# IORELAY8.net
KiCad netlist of a schematic drawn in EAGLE
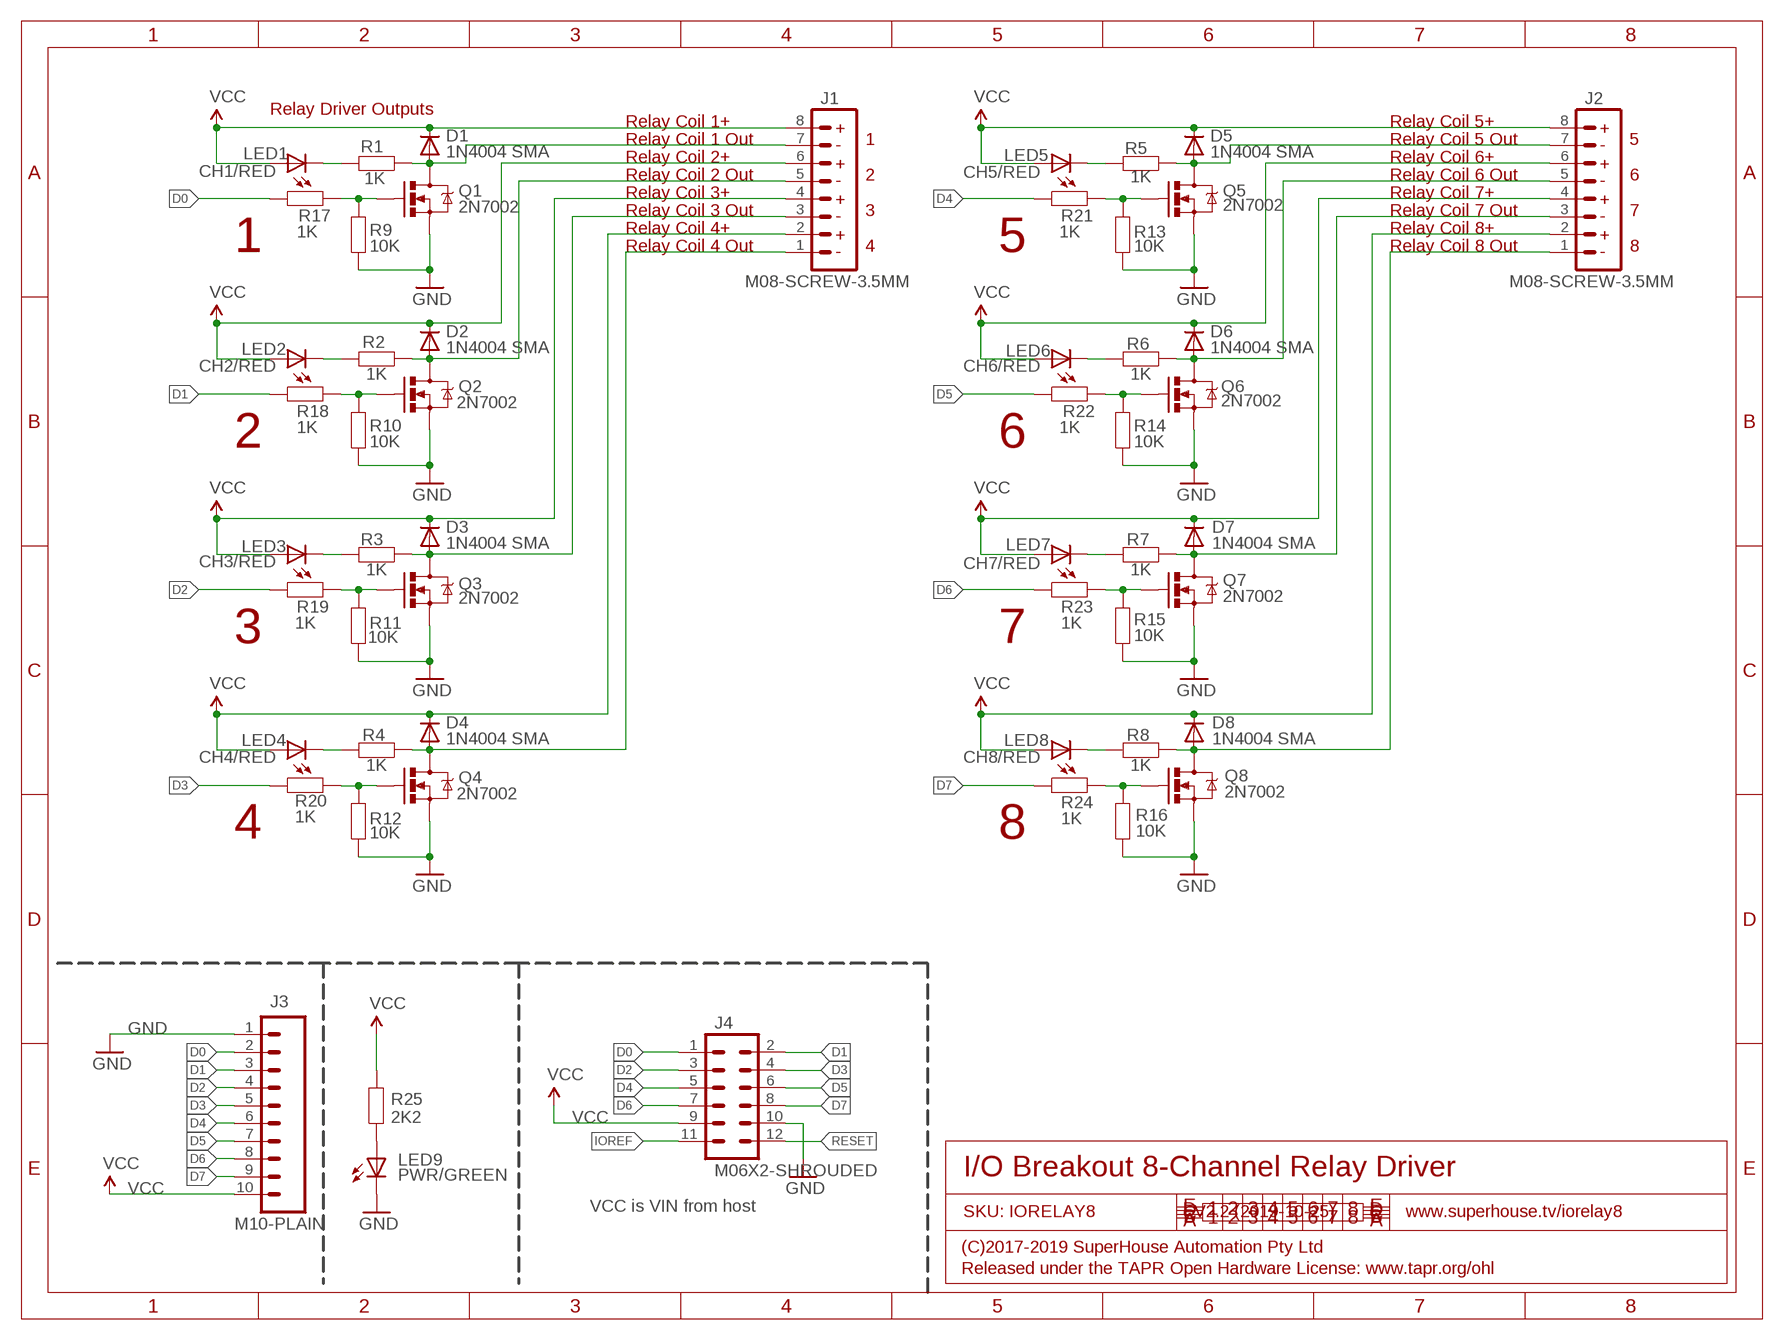
[diagram p0: schematic, sheet 1]

(export (version "E")
  (design (tool "Eeschema 10.0.6"))
  (components
    (comp (ref "D1")
      (value "1N4004 SMA")
      (footprint "eagle-import:SMA-DIODE")
      (libsource (lib "eagle-import") (part "DIODESMA"))
    )
    (comp (ref "D2")
      (value "1N4004 SMA")
      (footprint "eagle-import:SMA-DIODE")
      (libsource (lib "eagle-import") (part "DIODESMA"))
    )
    (comp (ref "D3")
      (value "1N4004 SMA")
      (footprint "eagle-import:SMA-DIODE")
      (libsource (lib "eagle-import") (part "DIODESMA"))
    )
    (comp (ref "D4")
      (value "1N4004 SMA")
      (footprint "eagle-import:SMA-DIODE")
      (libsource (lib "eagle-import") (part "DIODESMA"))
    )
    (comp (ref "D5")
      (value "1N4004 SMA")
      (footprint "eagle-import:SMA-DIODE")
      (libsource (lib "eagle-import") (part "DIODESMA"))
    )
    (comp (ref "D6")
      (value "1N4004 SMA")
      (footprint "eagle-import:SMA-DIODE")
      (libsource (lib "eagle-import") (part "DIODESMA"))
    )
    (comp (ref "D7")
      (value "1N4004 SMA")
      (footprint "eagle-import:SMA-DIODE")
      (libsource (lib "eagle-import") (part "DIODESMA"))
    )
    (comp (ref "D8")
      (value "1N4004 SMA")
      (footprint "eagle-import:SMA-DIODE")
      (libsource (lib "eagle-import") (part "DIODESMA"))
    )
    (comp (ref "J1")
      (value "M08-SCREW-3.5MM")
      (footprint "eagle-import:SCREWTERMINAL_3.5MM_8")
      (libsource (lib "eagle-import") (part "M08-SCREW-3.5MM"))
    )
    (comp (ref "J2")
      (value "M08-SCREW-3.5MM")
      (footprint "eagle-import:SCREWTERMINAL_3.5MM_8")
      (libsource (lib "eagle-import") (part "M08-SCREW-3.5MM"))
    )
    (comp (ref "J3")
      (value "M10-PLAIN")
      (footprint "eagle-import:1X10")
      (libsource (lib "eagle-import") (part "M10-PLAIN"))
    )
    (comp (ref "J4")
      (value "M06X2-SHROUDED")
      (footprint "eagle-import:2X6-SHROUDED")
      (libsource (lib "eagle-import") (part "M06X2-SHROUDED"))
    )
    (comp (ref "LED1")
      (value "CH1/RED")
      (footprint "eagle-import:LED-0603")
      (libsource (lib "eagle-import") (part "LED0603"))
    )
    (comp (ref "LED2")
      (value "CH2/RED")
      (footprint "eagle-import:LED-0603")
      (libsource (lib "eagle-import") (part "LED0603"))
    )
    (comp (ref "LED3")
      (value "CH3/RED")
      (footprint "eagle-import:LED-0603")
      (libsource (lib "eagle-import") (part "LED0603"))
    )
    (comp (ref "LED4")
      (value "CH4/RED")
      (footprint "eagle-import:LED-0603")
      (libsource (lib "eagle-import") (part "LED0603"))
    )
    (comp (ref "LED5")
      (value "CH5/RED")
      (footprint "eagle-import:LED-0603")
      (libsource (lib "eagle-import") (part "LED0603"))
    )
    (comp (ref "LED6")
      (value "CH6/RED")
      (footprint "eagle-import:LED-0603")
      (libsource (lib "eagle-import") (part "LED0603"))
    )
    (comp (ref "LED7")
      (value "CH7/RED")
      (footprint "eagle-import:LED-0603")
      (libsource (lib "eagle-import") (part "LED0603"))
    )
    (comp (ref "LED8")
      (value "CH8/RED")
      (footprint "eagle-import:LED-0603")
      (libsource (lib "eagle-import") (part "LED0603"))
    )
    (comp (ref "LED9")
      (value "PWR/GREEN")
      (footprint "eagle-import:LED-0603")
      (libsource (lib "eagle-import") (part "LED0603"))
    )
    (comp (ref "Q1")
      (value "2N7002")
      (footprint "eagle-import:SOT23-3")
      (libsource (lib "eagle-import") (part "MOSFET-NCHANNEL-233"))
    )
    (comp (ref "Q2")
      (value "2N7002")
      (footprint "eagle-import:SOT23-3")
      (libsource (lib "eagle-import") (part "MOSFET-NCHANNEL-233"))
    )
    (comp (ref "Q3")
      (value "2N7002")
      (footprint "eagle-import:SOT23-3")
      (libsource (lib "eagle-import") (part "MOSFET-NCHANNEL-233"))
    )
    (comp (ref "Q4")
      (value "2N7002")
      (footprint "eagle-import:SOT23-3")
      (libsource (lib "eagle-import") (part "MOSFET-NCHANNEL-233"))
    )
    (comp (ref "Q5")
      (value "2N7002")
      (footprint "eagle-import:SOT23-3")
      (libsource (lib "eagle-import") (part "MOSFET-NCHANNEL-233"))
    )
    (comp (ref "Q6")
      (value "2N7002")
      (footprint "eagle-import:SOT23-3")
      (libsource (lib "eagle-import") (part "MOSFET-NCHANNEL-233"))
    )
    (comp (ref "Q7")
      (value "2N7002")
      (footprint "eagle-import:SOT23-3")
      (libsource (lib "eagle-import") (part "MOSFET-NCHANNEL-233"))
    )
    (comp (ref "Q8")
      (value "2N7002")
      (footprint "eagle-import:SOT23-3")
      (libsource (lib "eagle-import") (part "MOSFET-NCHANNEL-233"))
    )
    (comp (ref "R1")
      (value "1K")
      (footprint "eagle-import:R0603")
      (libsource (lib "eagle-import") (part "RESISTOR0603"))
    )
    (comp (ref "R2")
      (value "1K")
      (footprint "eagle-import:R0603")
      (libsource (lib "eagle-import") (part "RESISTOR0603"))
    )
    (comp (ref "R3")
      (value "1K")
      (footprint "eagle-import:R0603")
      (libsource (lib "eagle-import") (part "RESISTOR0603"))
    )
    (comp (ref "R4")
      (value "1K")
      (footprint "eagle-import:R0603")
      (libsource (lib "eagle-import") (part "RESISTOR0603"))
    )
    (comp (ref "R5")
      (value "1K")
      (footprint "eagle-import:R0603")
      (libsource (lib "eagle-import") (part "RESISTOR0603"))
    )
    (comp (ref "R6")
      (value "1K")
      (footprint "eagle-import:R0603")
      (libsource (lib "eagle-import") (part "RESISTOR0603"))
    )
    (comp (ref "R7")
      (value "1K")
      (footprint "eagle-import:R0603")
      (libsource (lib "eagle-import") (part "RESISTOR0603"))
    )
    (comp (ref "R8")
      (value "1K")
      (footprint "eagle-import:R0603")
      (libsource (lib "eagle-import") (part "RESISTOR0603"))
    )
    (comp (ref "R9")
      (value "10K")
      (footprint "eagle-import:R0603")
      (libsource (lib "eagle-import") (part "RESISTOR0603"))
    )
    (comp (ref "R10")
      (value "10K")
      (footprint "eagle-import:R0603")
      (libsource (lib "eagle-import") (part "RESISTOR0603"))
    )
    (comp (ref "R11")
      (value "10K")
      (footprint "eagle-import:R0603")
      (libsource (lib "eagle-import") (part "RESISTOR0603"))
    )
    (comp (ref "R12")
      (value "10K")
      (footprint "eagle-import:R0603")
      (libsource (lib "eagle-import") (part "RESISTOR0603"))
    )
    (comp (ref "R13")
      (value "10K")
      (footprint "eagle-import:R0603")
      (libsource (lib "eagle-import") (part "RESISTOR0603"))
    )
    (comp (ref "R14")
      (value "10K")
      (footprint "eagle-import:R0603")
      (libsource (lib "eagle-import") (part "RESISTOR0603"))
    )
    (comp (ref "R15")
      (value "10K")
      (footprint "eagle-import:R0603")
      (libsource (lib "eagle-import") (part "RESISTOR0603"))
    )
    (comp (ref "R16")
      (value "10K")
      (footprint "eagle-import:R0603")
      (libsource (lib "eagle-import") (part "RESISTOR0603"))
    )
    (comp (ref "R17")
      (value "1K")
      (footprint "eagle-import:R0603")
      (libsource (lib "eagle-import") (part "RESISTOR0603"))
    )
    (comp (ref "R18")
      (value "1K")
      (footprint "eagle-import:R0603")
      (libsource (lib "eagle-import") (part "RESISTOR0603"))
    )
    (comp (ref "R19")
      (value "1K")
      (footprint "eagle-import:R0603")
      (libsource (lib "eagle-import") (part "RESISTOR0603"))
    )
    (comp (ref "R20")
      (value "1K")
      (footprint "eagle-import:R0603")
      (libsource (lib "eagle-import") (part "RESISTOR0603"))
    )
    (comp (ref "R21")
      (value "1K")
      (footprint "eagle-import:R0603")
      (libsource (lib "eagle-import") (part "RESISTOR0603"))
    )
    (comp (ref "R22")
      (value "1K")
      (footprint "eagle-import:R0603")
      (libsource (lib "eagle-import") (part "RESISTOR0603"))
    )
    (comp (ref "R23")
      (value "1K")
      (footprint "eagle-import:R0603")
      (libsource (lib "eagle-import") (part "RESISTOR0603"))
    )
    (comp (ref "R24")
      (value "1K")
      (footprint "eagle-import:R0603")
      (libsource (lib "eagle-import") (part "RESISTOR0603"))
    )
    (comp (ref "R25")
      (value "2K2")
      (footprint "eagle-import:R0603")
      (libsource (lib "eagle-import") (part "RESISTOR0603"))
    )
  )
  (nets
    (net (code "1") (name "D0") (class "Default")
      (node (ref "J3") (pin "2") (pinfunction "2_2") (pintype "passive"))
      (node (ref "J4") (pin "1") (pinfunction "1_1") (pintype "passive"))
      (node (ref "R17") (pin "2") (pinfunction "2_2") (pintype "passive"))
    )
    (net (code "2") (name "D1") (class "Default")
      (node (ref "J3") (pin "3") (pinfunction "3_3") (pintype "passive"))
      (node (ref "J4") (pin "2") (pinfunction "2_2") (pintype "passive"))
      (node (ref "R18") (pin "2") (pinfunction "2_2") (pintype "passive"))
    )
    (net (code "3") (name "D2") (class "Default")
      (node (ref "J3") (pin "4") (pinfunction "4_4") (pintype "passive"))
      (node (ref "J4") (pin "3") (pinfunction "3_3") (pintype "passive"))
      (node (ref "R19") (pin "2") (pinfunction "2_2") (pintype "passive"))
    )
    (net (code "4") (name "D3") (class "Default")
      (node (ref "J3") (pin "5") (pinfunction "5_5") (pintype "passive"))
      (node (ref "J4") (pin "4") (pinfunction "4_4") (pintype "passive"))
      (node (ref "R20") (pin "2") (pinfunction "2_2") (pintype "passive"))
    )
    (net (code "5") (name "D4") (class "Default")
      (node (ref "J3") (pin "6") (pinfunction "6_6") (pintype "passive"))
      (node (ref "J4") (pin "5") (pinfunction "5_5") (pintype "passive"))
      (node (ref "R21") (pin "2") (pinfunction "2_2") (pintype "passive"))
    )
    (net (code "6") (name "D5") (class "Default")
      (node (ref "J3") (pin "7") (pinfunction "7_7") (pintype "passive"))
      (node (ref "J4") (pin "6") (pinfunction "6_6") (pintype "passive"))
      (node (ref "R22") (pin "2") (pinfunction "2_2") (pintype "passive"))
    )
    (net (code "7") (name "D6") (class "Default")
      (node (ref "J3") (pin "8") (pinfunction "8_8") (pintype "passive"))
      (node (ref "J4") (pin "7") (pinfunction "7_7") (pintype "passive"))
      (node (ref "R23") (pin "2") (pinfunction "2_2") (pintype "passive"))
    )
    (net (code "8") (name "D7") (class "Default")
      (node (ref "J3") (pin "9") (pinfunction "9_9") (pintype "passive"))
      (node (ref "J4") (pin "8") (pinfunction "8_8") (pintype "passive"))
      (node (ref "R24") (pin "2") (pinfunction "2_2") (pintype "passive"))
    )
    (net (code "9") (name "GND") (class "Default")
      (node (ref "J3") (pin "1") (pinfunction "1_1") (pintype "passive"))
      (node (ref "J4") (pin "10") (pinfunction "10_10") (pintype "passive"))
      (node (ref "LED9") (pin "C") (pinfunction "C_C") (pintype "passive"))
      (node (ref "Q1") (pin "2") (pinfunction "S_2") (pintype "passive"))
      (node (ref "Q2") (pin "2") (pinfunction "S_2") (pintype "passive"))
      (node (ref "Q3") (pin "2") (pinfunction "S_2") (pintype "passive"))
      (node (ref "Q4") (pin "2") (pinfunction "S_2") (pintype "passive"))
      (node (ref "Q5") (pin "2") (pinfunction "S_2") (pintype "passive"))
      (node (ref "Q6") (pin "2") (pinfunction "S_2") (pintype "passive"))
      (node (ref "Q7") (pin "2") (pinfunction "S_2") (pintype "passive"))
      (node (ref "Q8") (pin "2") (pinfunction "S_2") (pintype "passive"))
      (node (ref "R10") (pin "1") (pinfunction "1_1") (pintype "passive"))
      (node (ref "R11") (pin "1") (pinfunction "1_1") (pintype "passive"))
      (node (ref "R12") (pin "1") (pinfunction "1_1") (pintype "passive"))
      (node (ref "R13") (pin "1") (pinfunction "1_1") (pintype "passive"))
      (node (ref "R14") (pin "1") (pinfunction "1_1") (pintype "passive"))
      (node (ref "R15") (pin "1") (pinfunction "1_1") (pintype "passive"))
      (node (ref "R16") (pin "1") (pinfunction "1_1") (pintype "passive"))
      (node (ref "R9") (pin "1") (pinfunction "1_1") (pintype "passive"))
    )
    (net (code "10") (name "IOREF") (class "Default")
      (node (ref "J4") (pin "11") (pinfunction "11_11") (pintype "passive"))
    )
    (net (code "11") (name "Net-(LED1-PadC)") (class "Default")
      (node (ref "LED1") (pin "C") (pinfunction "C_C") (pintype "passive"))
      (node (ref "R1") (pin "1") (pinfunction "1_1") (pintype "passive"))
    )
    (net (code "12") (name "Net-(LED2-PadC)") (class "Default")
      (node (ref "LED2") (pin "C") (pinfunction "C_C") (pintype "passive"))
      (node (ref "R2") (pin "1") (pinfunction "1_1") (pintype "passive"))
    )
    (net (code "13") (name "Net-(LED3-PadC)") (class "Default")
      (node (ref "LED3") (pin "C") (pinfunction "C_C") (pintype "passive"))
      (node (ref "R3") (pin "1") (pinfunction "1_1") (pintype "passive"))
    )
    (net (code "14") (name "Net-(LED4-PadC)") (class "Default")
      (node (ref "LED4") (pin "C") (pinfunction "C_C") (pintype "passive"))
      (node (ref "R4") (pin "1") (pinfunction "1_1") (pintype "passive"))
    )
    (net (code "15") (name "Net-(LED5-PadC)") (class "Default")
      (node (ref "LED5") (pin "C") (pinfunction "C_C") (pintype "passive"))
      (node (ref "R5") (pin "1") (pinfunction "1_1") (pintype "passive"))
    )
    (net (code "16") (name "Net-(LED6-PadC)") (class "Default")
      (node (ref "LED6") (pin "C") (pinfunction "C_C") (pintype "passive"))
      (node (ref "R6") (pin "1") (pinfunction "1_1") (pintype "passive"))
    )
    (net (code "17") (name "Net-(LED7-PadC)") (class "Default")
      (node (ref "LED7") (pin "C") (pinfunction "C_C") (pintype "passive"))
      (node (ref "R7") (pin "1") (pinfunction "1_1") (pintype "passive"))
    )
    (net (code "18") (name "Net-(LED8-PadC)") (class "Default")
      (node (ref "LED8") (pin "C") (pinfunction "C_C") (pintype "passive"))
      (node (ref "R8") (pin "1") (pinfunction "1_1") (pintype "passive"))
    )
    (net (code "19") (name "Net-(LED9-PadA)") (class "Default")
      (node (ref "LED9") (pin "A") (pinfunction "A_A") (pintype "passive"))
      (node (ref "R25") (pin "1") (pinfunction "1_1") (pintype "passive"))
    )
    (net (code "20") (name "Net-(Q1-D)") (class "Default")
      (node (ref "D1") (pin "A") (pinfunction "A_A") (pintype "passive"))
      (node (ref "J1") (pin "7") (pinfunction "7_7") (pintype "passive"))
      (node (ref "Q1") (pin "3") (pinfunction "D_3") (pintype "passive"))
      (node (ref "R1") (pin "2") (pinfunction "2_2") (pintype "passive"))
    )
    (net (code "21") (name "Net-(Q1-G)") (class "Default")
      (node (ref "Q1") (pin "1") (pinfunction "G_1") (pintype "passive"))
      (node (ref "R17") (pin "1") (pinfunction "1_1") (pintype "passive"))
      (node (ref "R9") (pin "2") (pinfunction "2_2") (pintype "passive"))
    )
    (net (code "22") (name "Net-(Q2-D)") (class "Default")
      (node (ref "D2") (pin "A") (pinfunction "A_A") (pintype "passive"))
      (node (ref "J1") (pin "5") (pinfunction "5_5") (pintype "passive"))
      (node (ref "Q2") (pin "3") (pinfunction "D_3") (pintype "passive"))
      (node (ref "R2") (pin "2") (pinfunction "2_2") (pintype "passive"))
    )
    (net (code "23") (name "Net-(Q2-G)") (class "Default")
      (node (ref "Q2") (pin "1") (pinfunction "G_1") (pintype "passive"))
      (node (ref "R10") (pin "2") (pinfunction "2_2") (pintype "passive"))
      (node (ref "R18") (pin "1") (pinfunction "1_1") (pintype "passive"))
    )
    (net (code "24") (name "Net-(Q3-D)") (class "Default")
      (node (ref "D3") (pin "A") (pinfunction "A_A") (pintype "passive"))
      (node (ref "J1") (pin "3") (pinfunction "3_3") (pintype "passive"))
      (node (ref "Q3") (pin "3") (pinfunction "D_3") (pintype "passive"))
      (node (ref "R3") (pin "2") (pinfunction "2_2") (pintype "passive"))
    )
    (net (code "25") (name "Net-(Q3-G)") (class "Default")
      (node (ref "Q3") (pin "1") (pinfunction "G_1") (pintype "passive"))
      (node (ref "R11") (pin "2") (pinfunction "2_2") (pintype "passive"))
      (node (ref "R19") (pin "1") (pinfunction "1_1") (pintype "passive"))
    )
    (net (code "26") (name "Net-(Q4-D)") (class "Default")
      (node (ref "D4") (pin "A") (pinfunction "A_A") (pintype "passive"))
      (node (ref "J1") (pin "1") (pinfunction "1_1") (pintype "passive"))
      (node (ref "Q4") (pin "3") (pinfunction "D_3") (pintype "passive"))
      (node (ref "R4") (pin "2") (pinfunction "2_2") (pintype "passive"))
    )
    (net (code "27") (name "Net-(Q4-G)") (class "Default")
      (node (ref "Q4") (pin "1") (pinfunction "G_1") (pintype "passive"))
      (node (ref "R12") (pin "2") (pinfunction "2_2") (pintype "passive"))
      (node (ref "R20") (pin "1") (pinfunction "1_1") (pintype "passive"))
    )
    (net (code "28") (name "Net-(Q5-D)") (class "Default")
      (node (ref "D5") (pin "A") (pinfunction "A_A") (pintype "passive"))
      (node (ref "J2") (pin "7") (pinfunction "7_7") (pintype "passive"))
      (node (ref "Q5") (pin "3") (pinfunction "D_3") (pintype "passive"))
      (node (ref "R5") (pin "2") (pinfunction "2_2") (pintype "passive"))
    )
    (net (code "29") (name "Net-(Q5-G)") (class "Default")
      (node (ref "Q5") (pin "1") (pinfunction "G_1") (pintype "passive"))
      (node (ref "R13") (pin "2") (pinfunction "2_2") (pintype "passive"))
      (node (ref "R21") (pin "1") (pinfunction "1_1") (pintype "passive"))
    )
    (net (code "30") (name "Net-(Q6-D)") (class "Default")
      (node (ref "D6") (pin "A") (pinfunction "A_A") (pintype "passive"))
      (node (ref "J2") (pin "5") (pinfunction "5_5") (pintype "passive"))
      (node (ref "Q6") (pin "3") (pinfunction "D_3") (pintype "passive"))
      (node (ref "R6") (pin "2") (pinfunction "2_2") (pintype "passive"))
    )
    (net (code "31") (name "Net-(Q6-G)") (class "Default")
      (node (ref "Q6") (pin "1") (pinfunction "G_1") (pintype "passive"))
      (node (ref "R14") (pin "2") (pinfunction "2_2") (pintype "passive"))
      (node (ref "R22") (pin "1") (pinfunction "1_1") (pintype "passive"))
    )
    (net (code "32") (name "Net-(Q7-D)") (class "Default")
      (node (ref "D7") (pin "A") (pinfunction "A_A") (pintype "passive"))
      (node (ref "J2") (pin "3") (pinfunction "3_3") (pintype "passive"))
      (node (ref "Q7") (pin "3") (pinfunction "D_3") (pintype "passive"))
      (node (ref "R7") (pin "2") (pinfunction "2_2") (pintype "passive"))
    )
    (net (code "33") (name "Net-(Q7-G)") (class "Default")
      (node (ref "Q7") (pin "1") (pinfunction "G_1") (pintype "passive"))
      (node (ref "R15") (pin "2") (pinfunction "2_2") (pintype "passive"))
      (node (ref "R23") (pin "1") (pinfunction "1_1") (pintype "passive"))
    )
    (net (code "34") (name "Net-(Q8-D)") (class "Default")
      (node (ref "D8") (pin "A") (pinfunction "A_A") (pintype "passive"))
      (node (ref "J2") (pin "1") (pinfunction "1_1") (pintype "passive"))
      (node (ref "Q8") (pin "3") (pinfunction "D_3") (pintype "passive"))
      (node (ref "R8") (pin "2") (pinfunction "2_2") (pintype "passive"))
    )
    (net (code "35") (name "Net-(Q8-G)") (class "Default")
      (node (ref "Q8") (pin "1") (pinfunction "G_1") (pintype "passive"))
      (node (ref "R16") (pin "2") (pinfunction "2_2") (pintype "passive"))
      (node (ref "R24") (pin "1") (pinfunction "1_1") (pintype "passive"))
    )
    (net (code "36") (name "RESET") (class "Default")
      (node (ref "J4") (pin "12") (pinfunction "12_12") (pintype "passive"))
    )
    (net (code "37") (name "VCC") (class "Default")
      (node (ref "D1") (pin "C") (pinfunction "C_C") (pintype "passive"))
      (node (ref "D2") (pin "C") (pinfunction "C_C") (pintype "passive"))
      (node (ref "D3") (pin "C") (pinfunction "C_C") (pintype "passive"))
      (node (ref "D4") (pin "C") (pinfunction "C_C") (pintype "passive"))
      (node (ref "D5") (pin "C") (pinfunction "C_C") (pintype "passive"))
      (node (ref "D6") (pin "C") (pinfunction "C_C") (pintype "passive"))
      (node (ref "D7") (pin "C") (pinfunction "C_C") (pintype "passive"))
      (node (ref "D8") (pin "C") (pinfunction "C_C") (pintype "passive"))
      (node (ref "J1") (pin "2") (pinfunction "2_2") (pintype "passive"))
      (node (ref "J1") (pin "4") (pinfunction "4_4") (pintype "passive"))
      (node (ref "J1") (pin "6") (pinfunction "6_6") (pintype "passive"))
      (node (ref "J1") (pin "8") (pinfunction "8_8") (pintype "passive"))
      (node (ref "J2") (pin "2") (pinfunction "2_2") (pintype "passive"))
      (node (ref "J2") (pin "4") (pinfunction "4_4") (pintype "passive"))
      (node (ref "J2") (pin "6") (pinfunction "6_6") (pintype "passive"))
      (node (ref "J2") (pin "8") (pinfunction "8_8") (pintype "passive"))
      (node (ref "J3") (pin "10") (pinfunction "10_10") (pintype "passive"))
      (node (ref "J4") (pin "9") (pinfunction "9_9") (pintype "passive"))
      (node (ref "LED1") (pin "A") (pinfunction "A_A") (pintype "passive"))
      (node (ref "LED2") (pin "A") (pinfunction "A_A") (pintype "passive"))
      (node (ref "LED3") (pin "A") (pinfunction "A_A") (pintype "passive"))
      (node (ref "LED4") (pin "A") (pinfunction "A_A") (pintype "passive"))
      (node (ref "LED5") (pin "A") (pinfunction "A_A") (pintype "passive"))
      (node (ref "LED6") (pin "A") (pinfunction "A_A") (pintype "passive"))
      (node (ref "LED7") (pin "A") (pinfunction "A_A") (pintype "passive"))
      (node (ref "LED8") (pin "A") (pinfunction "A_A") (pintype "passive"))
      (node (ref "R25") (pin "2") (pinfunction "2_2") (pintype "passive"))
    )
  )
)
